# GaN_LLC.net
KiCad netlist of a schematic drawn in Altium Designer
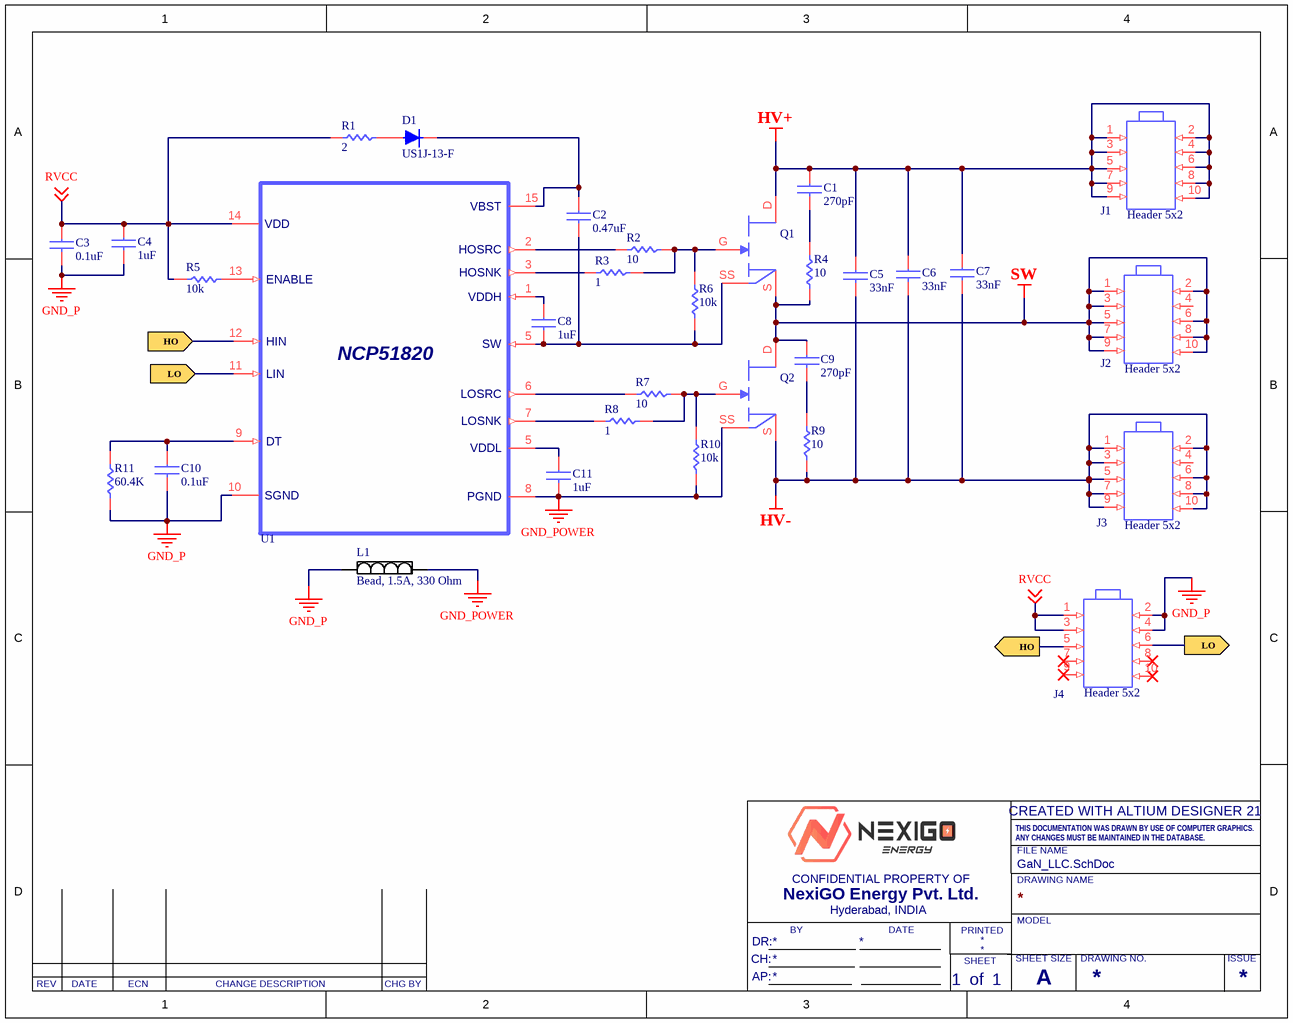
[diagram p0: GaN_LLC.SchDoc]

(export (version "E")
  (design (tool "Eeschema 10.0.6"))
  (components
    (comp (ref "C1")
      (value "270pF")
      (footprint "1206")
      (description "CAP CER 270PF 1KV C0G/NP0 1206")
      (fields (field (name "TOLERANCE") "±5%") (field (name "MANUFACTURER") "Samsung Electro-Mechanics"))
      (libsource (lib "NexiGOEnergyPartsDatabaseLibrary") (part "CAP_CERAMIC"))
    )
    (comp (ref "C2")
      (value "0.47uF")
      (footprint "Cap, 0603")
      (description "CAP CER 0.47UF 25V 10% X7R 0603")
      (fields (field (name "TOLERANCE") "10%") (field (name "MANUFACTURER") "AVX Corporation"))
      (libsource (lib "NexiGOEnergyPartsDatabaseLibrary") (part "CAP_CERAMIC"))
    )
    (comp (ref "C3")
      (value "0.1uF")
      (footprint "Cap, 0603")
      (description "CAP CER 0.1UF 50V 10% X7R 0603")
      (fields (field (name "TOLERANCE") "10%") (field (name "MANUFACTURER") "TAIYO YUDEN"))
      (libsource (lib "NexiGOEnergyPartsDatabaseLibrary") (part "CAP_CERAMIC"))
    )
    (comp (ref "C4")
      (value "1uF")
      (footprint "Cap, 0603")
      (description "CAP CER 1UF 25V 10% X7R 0603")
      (fields (field (name "TOLERANCE") "10%") (field (name "MANUFACTURER") "Samsung Electro-Mechanics"))
      (libsource (lib "NexiGOEnergyPartsDatabaseLibrary") (part "CAP_CERAMIC"))
    )
    (comp (ref "C5")
      (value "33nF")
      (footprint "1210")
      (description "CAP CER 0.033UF 1.5KV X7R 1210")
      (fields (field (name "TOLERANCE") "10%") (field (name "MANUFACTURER") "KEMET"))
      (libsource (lib "NexiGOEnergyPartsDatabaseLibrary") (part "CAP_CERAMIC"))
    )
    (comp (ref "C6")
      (value "33nF")
      (footprint "1210")
      (description "CAP CER 0.033UF 1.5KV X7R 1210")
      (fields (field (name "TOLERANCE") "10%") (field (name "MANUFACTURER") "KEMET"))
      (libsource (lib "NexiGOEnergyPartsDatabaseLibrary") (part "CAP_CERAMIC"))
    )
    (comp (ref "C7")
      (value "33nF")
      (footprint "1210")
      (description "CAP CER 0.033UF 1.5KV X7R 1210")
      (fields (field (name "TOLERANCE") "10%") (field (name "MANUFACTURER") "KEMET"))
      (libsource (lib "NexiGOEnergyPartsDatabaseLibrary") (part "CAP_CERAMIC"))
    )
    (comp (ref "C8")
      (value "1uF")
      (footprint "Cap, 0603")
      (description "CAP CER 1UF 25V 10% X7R 0603")
      (fields (field (name "TOLERANCE") "10%") (field (name "MANUFACTURER") "Samsung Electro-Mechanics"))
      (libsource (lib "NexiGOEnergyPartsDatabaseLibrary") (part "CAP_CERAMIC"))
    )
    (comp (ref "C9")
      (value "270pF")
      (footprint "1206")
      (description "CAP CER 270PF 1KV C0G/NP0 1206")
      (fields (field (name "TOLERANCE") "±5%") (field (name "MANUFACTURER") "Samsung Electro-Mechanics"))
      (libsource (lib "NexiGOEnergyPartsDatabaseLibrary") (part "CAP_CERAMIC"))
    )
    (comp (ref "C10")
      (value "0.1uF")
      (footprint "Cap, 0603")
      (description "CAP CER 0.1UF 50V 10% X7R 0603")
      (fields (field (name "TOLERANCE") "10%") (field (name "MANUFACTURER") "TAIYO YUDEN"))
      (libsource (lib "NexiGOEnergyPartsDatabaseLibrary") (part "CAP_CERAMIC"))
    )
    (comp (ref "C11")
      (value "1uF")
      (footprint "Cap, 0603")
      (description "CAP CER 1UF 25V 10% X7R 0603")
      (fields (field (name "TOLERANCE") "10%") (field (name "MANUFACTURER") "Samsung Electro-Mechanics"))
      (libsource (lib "NexiGOEnergyPartsDatabaseLibrary") (part "CAP_CERAMIC"))
    )
    (comp (ref "D1")
      (value "US1J-13-F")
      (footprint "SMA")
      (description "DIODE GEN PURP 600V 1A SMA")
      (fields (field (name "MANUFACTURER") "Diodes Incorporated") (field (name "Comment") "Diode"))
      (libsource (lib "NexiGOEnergyPartsDatabaseLibrary") (part "Diode"))
    )
    (comp (ref "J1")
      (value "Header 5x2")
      (footprint "HDR2X5_SMD")
      (description "HEADER 5X2 2MM Pitch SMT")
      (fields
        (field (name "MANUFACTURER") "Sullins Connector Solutions")
        (field (name "Comment") "Header 5x2, 100Mils")
      )
      (libsource (lib "NexiGOEnergyPartsDatabaseLibrary") (part "Header 5x2, 100Mils"))
    )
    (comp (ref "J2")
      (value "Header 5x2")
      (footprint "HDR2X5_SMD")
      (description "HEADER 5X2 2MM Pitch SMT")
      (fields
        (field (name "MANUFACTURER") "Sullins Connector Solutions")
        (field (name "Comment") "Header 5x2, 100Mils")
      )
      (libsource (lib "NexiGOEnergyPartsDatabaseLibrary") (part "Header 5x2, 100Mils"))
    )
    (comp (ref "J3")
      (value "Header 5x2")
      (footprint "HDR2X5_SMD")
      (description "HEADER 5X2 2MM Pitch SMT")
      (fields
        (field (name "MANUFACTURER") "Sullins Connector Solutions")
        (field (name "Comment") "Header 5x2, 100Mils")
      )
      (libsource (lib "NexiGOEnergyPartsDatabaseLibrary") (part "Header 5x2, 100Mils"))
    )
    (comp (ref "J4")
      (value "Header 5x2")
      (footprint "HDR2X5_SMD")
      (description "HEADER 5X2 2MM Pitch SMT")
      (fields
        (field (name "MANUFACTURER") "Sullins Connector Solutions")
        (field (name "Comment") "Header 5x2, 100Mils")
      )
      (libsource (lib "NexiGOEnergyPartsDatabaseLibrary") (part "Header 5x2, 100Mils"))
    )
    (comp (ref "L1")
      (value "Bead, 1.5A, 330 Ohm")
      (footprint "0603")
      (description "FERRITE BEAD 330 OHM 1.5A 0603")
      (fields (field (name "MANUFACTURER") "Murata") (field (name "Comment") "Bead, 6A, 33 Ohm"))
      (libsource (lib "NexiGOEnergyPartsDatabaseLibrary") (part "Bead, 6A, 33 Ohm"))
    )
    (comp (ref "Q1")
      (value "GS66508B")
      (footprint "GS66508B")
      (description "GS66508B GaN FET 650V 30A 50mOhm SMT")
      (fields (field (name "MANUFACTURER") "GaN Systems"))
      (libsource (lib "NexiGOEnergyPartsDatabaseLibrary") (part "GS66508B"))
    )
    (comp (ref "Q2")
      (value "GS66508B")
      (footprint "GS66508B")
      (description "GS66508B GaN FET 650V 30A 50mOhm SMT")
      (fields (field (name "MANUFACTURER") "GaN Systems"))
      (libsource (lib "NexiGOEnergyPartsDatabaseLibrary") (part "GS66508B"))
    )
    (comp (ref "R1")
      (value "2")
      (footprint "Res, 0603")
      (description "RES 2 OHM 1/10W 1% 0603 SMD")
      (fields (field (name "MANUFACTURER") "Vishay / Dale") (field (name "TOLERANCE") "±1%"))
      (libsource (lib "NexiGOEnergyPartsDatabaseLibrary") (part "Res"))
    )
    (comp (ref "R2")
      (value "10")
      (footprint "Res, 0603")
      (description "Res, 10, 1%, 0603,1/10W, Panasonic, 100ppm")
      (fields (field (name "MANUFACTURER") "Panasonic") (field (name "TOLERANCE") "±1%"))
      (libsource (lib "NexiGOEnergyPartsDatabaseLibrary") (part "Res"))
    )
    (comp (ref "R3")
      (value "1")
      (footprint "Res, 0603")
      (description "RES 1 OHM 1/10W 0603")
      (fields (field (name "MANUFACTURER") "Vishay/Dale") (field (name "TOLERANCE") "±1%"))
      (libsource (lib "NexiGOEnergyPartsDatabaseLibrary") (part "Res"))
    )
    (comp (ref "R4")
      (value "10")
      (footprint "Res_2512")
      (description "RES 10 OHM 5% 2W 2512")
      (fields (field (name "MANUFACTURER") "YAGEO") (field (name "TOLERANCE") "5%"))
      (libsource (lib "NexiGOEnergyPartsDatabaseLibrary") (part "Res"))
    )
    (comp (ref "R5")
      (value "10k")
      (footprint "Res, 0603")
      (description "Res, 10K, 1%, 0603,1/10W, Panasonic, 100ppm")
      (fields (field (name "MANUFACTURER") "Panasonic") (field (name "TOLERANCE") "±1%"))
      (libsource (lib "NexiGOEnergyPartsDatabaseLibrary") (part "Res"))
    )
    (comp (ref "R6")
      (value "10k")
      (footprint "Res, 0603")
      (description "Res, 10K, 1%, 0603,1/10W, Panasonic, 100ppm")
      (fields (field (name "MANUFACTURER") "Panasonic") (field (name "TOLERANCE") "±1%"))
      (libsource (lib "NexiGOEnergyPartsDatabaseLibrary") (part "Res"))
    )
    (comp (ref "R7")
      (value "10")
      (footprint "Res, 0603")
      (description "Res, 10, 1%, 0603,1/10W, Panasonic, 100ppm")
      (fields (field (name "MANUFACTURER") "Panasonic") (field (name "TOLERANCE") "±1%"))
      (libsource (lib "NexiGOEnergyPartsDatabaseLibrary") (part "Res"))
    )
    (comp (ref "R8")
      (value "1")
      (footprint "Res, 0603")
      (description "RES 1 OHM 1/10W 0603")
      (fields (field (name "MANUFACTURER") "Vishay/Dale") (field (name "TOLERANCE") "±1%"))
      (libsource (lib "NexiGOEnergyPartsDatabaseLibrary") (part "Res"))
    )
    (comp (ref "R9")
      (value "10")
      (footprint "Res_2512")
      (description "RES 10 OHM 5% 2W 2512")
      (fields (field (name "MANUFACTURER") "YAGEO") (field (name "TOLERANCE") "5%"))
      (libsource (lib "NexiGOEnergyPartsDatabaseLibrary") (part "Res"))
    )
    (comp (ref "R10")
      (value "10k")
      (footprint "Res, 0603")
      (description "Res, 10K, 1%, 0603,1/10W, Panasonic, 100ppm")
      (fields (field (name "MANUFACTURER") "Panasonic") (field (name "TOLERANCE") "±1%"))
      (libsource (lib "NexiGOEnergyPartsDatabaseLibrary") (part "Res"))
    )
    (comp (ref "R11")
      (value "60.4K")
      (footprint "Res, 0603")
      (description "RES 60.4K OHM 1/10W 1% 0603 SMD")
      (fields (field (name "MANUFACTURER") "Panasonic") (field (name "TOLERANCE") "±1%"))
      (libsource (lib "NexiGOEnergyPartsDatabaseLibrary") (part "Res"))
    )
    (comp (ref "U1")
      (value "NCP51820")
      (footprint "QFN_0AMNTWG_ONS")
      (description "NCP51820 FULL BRIDGE GATE DRIVE 15QFN SMD")
      (fields (field (name "MANUFACTURER") "Onsemi"))
      (libsource (lib "NexiGOEnergyPartsDatabaseLibrary") (part "NCP51820"))
    )
  )
  (nets
    (net (code "1") (name "/HO") (class "Default")
      (node (ref "J4") (pin "5") (pintype "input"))
      (node (ref "U1") (pin "12") (pinfunction "HIN_12") (pintype "input"))
    )
    (net (code "2") (name "/LO") (class "Default")
      (node (ref "J4") (pin "6") (pintype "input"))
      (node (ref "U1") (pin "11") (pinfunction "LIN_11") (pintype "input"))
    )
    (net (code "3") (name "GND_P") (class "Default")
      (node (ref "C10") (pin "2") (pinfunction "2_2") (pintype "passive"))
      (node (ref "C3") (pin "2") (pinfunction "2_2") (pintype "passive"))
      (node (ref "C4") (pin "2") (pinfunction "2_2") (pintype "passive"))
      (node (ref "J4") (pin "2") (pintype "input"))
      (node (ref "J4") (pin "4") (pintype "input"))
      (node (ref "L1") (pin "1") (pinfunction "1_1") (pintype "passive"))
      (node (ref "R11") (pin "1") (pinfunction "1_1") (pintype "passive"))
      (node (ref "U1") (pin "10") (pinfunction "SGND_10") (pintype "power_in"))
    )
    (net (code "4") (name "GND_POWER") (class "Default")
      (node (ref "C11") (pin "2") (pinfunction "2_2") (pintype "passive"))
      (node (ref "L1") (pin "2") (pinfunction "2_2") (pintype "passive"))
      (node (ref "Q2") (pin "SS") (pinfunction "SS_SS") (pintype "passive"))
      (node (ref "R10") (pin "1") (pinfunction "1_1") (pintype "passive"))
      (node (ref "U1") (pin "8") (pinfunction "PGND_8") (pintype "power_in"))
    )
    (net (code "5") (name "HV+") (class "Default")
      (node (ref "C1") (pin "1") (pinfunction "1_1") (pintype "passive"))
      (node (ref "C5") (pin "1") (pinfunction "1_1") (pintype "passive"))
      (node (ref "C6") (pin "1") (pinfunction "1_1") (pintype "passive"))
      (node (ref "C7") (pin "1") (pinfunction "1_1") (pintype "passive"))
      (node (ref "J1") (pin "1") (pintype "input"))
      (node (ref "J1") (pin "10") (pintype "input"))
      (node (ref "J1") (pin "2") (pintype "input"))
      (node (ref "J1") (pin "3") (pintype "input"))
      (node (ref "J1") (pin "4") (pintype "input"))
      (node (ref "J1") (pin "5") (pintype "input"))
      (node (ref "J1") (pin "6") (pintype "input"))
      (node (ref "J1") (pin "7") (pintype "input"))
      (node (ref "J1") (pin "8") (pintype "input"))
      (node (ref "J1") (pin "9") (pintype "input"))
      (node (ref "Q1") (pin "D") (pinfunction "D_D") (pintype "passive"))
    )
    (net (code "6") (name "HV-") (class "Default")
      (node (ref "C5") (pin "2") (pinfunction "2_2") (pintype "passive"))
      (node (ref "C6") (pin "2") (pinfunction "2_2") (pintype "passive"))
      (node (ref "C7") (pin "2") (pinfunction "2_2") (pintype "passive"))
      (node (ref "J3") (pin "1") (pintype "input"))
      (node (ref "J3") (pin "10") (pintype "input"))
      (node (ref "J3") (pin "2") (pintype "input"))
      (node (ref "J3") (pin "3") (pintype "input"))
      (node (ref "J3") (pin "5") (pintype "input"))
      (node (ref "J3") (pin "6") (pintype "input"))
      (node (ref "J3") (pin "7") (pintype "input"))
      (node (ref "J3") (pin "8") (pintype "input"))
      (node (ref "J3") (pin "9") (pintype "input"))
      (node (ref "Q2") (pin "S") (pinfunction "S_S") (pintype "passive"))
      (node (ref "R9") (pin "1") (pinfunction "1_1") (pintype "passive"))
    )
    (net (code "7") (name "Net-(C1-Pad2)") (class "Default")
      (node (ref "C1") (pin "2") (pinfunction "2_2") (pintype "passive"))
      (node (ref "R4") (pin "2") (pinfunction "2_2") (pintype "passive"))
    )
    (net (code "8") (name "Net-(C9-Pad2)") (class "Default")
      (node (ref "C9") (pin "2") (pinfunction "2_2") (pintype "passive"))
      (node (ref "R9") (pin "2") (pinfunction "2_2") (pintype "passive"))
    )
    (net (code "9") (name "Net-(D1-Pad2)") (class "Default")
      (node (ref "D1") (pin "2") (pinfunction "2_2") (pintype "passive"))
      (node (ref "R1") (pin "2") (pinfunction "2_2") (pintype "passive"))
    )
    (net (code "10") (name "Net-(Q1-PadG)") (class "Default")
      (node (ref "Q1") (pin "G") (pinfunction "G_G") (pintype "passive"))
      (node (ref "R2") (pin "2") (pinfunction "2_2") (pintype "passive"))
      (node (ref "R3") (pin "2") (pinfunction "2_2") (pintype "passive"))
      (node (ref "R6") (pin "2") (pinfunction "2_2") (pintype "passive"))
    )
    (net (code "11") (name "Net-(Q2-PadG)") (class "Default")
      (node (ref "Q2") (pin "G") (pinfunction "G_G") (pintype "passive"))
      (node (ref "R10") (pin "2") (pinfunction "2_2") (pintype "passive"))
      (node (ref "R7") (pin "2") (pinfunction "2_2") (pintype "passive"))
      (node (ref "R8") (pin "2") (pinfunction "2_2") (pintype "passive"))
    )
    (net (code "12") (name "Net-(U1-DT)") (class "Default")
      (node (ref "C10") (pin "1") (pinfunction "1_1") (pintype "passive"))
      (node (ref "R11") (pin "2") (pinfunction "2_2") (pintype "passive"))
      (node (ref "U1") (pin "9") (pinfunction "DT_9") (pintype "input"))
    )
    (net (code "13") (name "Net-(U1-ENABLE)") (class "Default")
      (node (ref "R5") (pin "1") (pinfunction "1_1") (pintype "passive"))
      (node (ref "U1") (pin "13") (pinfunction "ENABLE_13") (pintype "input"))
    )
    (net (code "14") (name "Net-(U1-HOSNK)") (class "Default")
      (node (ref "R3") (pin "1") (pinfunction "1_1") (pintype "passive"))
      (node (ref "U1") (pin "3") (pinfunction "HOSNK_3") (pintype "output"))
    )
    (net (code "15") (name "Net-(U1-HOSRC)") (class "Default")
      (node (ref "R2") (pin "1") (pinfunction "1_1") (pintype "passive"))
      (node (ref "U1") (pin "2") (pinfunction "HOSRC_2") (pintype "output"))
    )
    (net (code "16") (name "Net-(U1-LOSNK)") (class "Default")
      (node (ref "R8") (pin "1") (pinfunction "1_1") (pintype "passive"))
      (node (ref "U1") (pin "7") (pinfunction "LOSNK_7") (pintype "output"))
    )
    (net (code "17") (name "Net-(U1-LOSRC)") (class "Default")
      (node (ref "R7") (pin "1") (pinfunction "1_1") (pintype "passive"))
      (node (ref "U1") (pin "6") (pinfunction "LOSRC_6") (pintype "output"))
    )
    (net (code "18") (name "Net-(U1-SW)") (class "Default")
      (node (ref "C2") (pin "2") (pinfunction "2_2") (pintype "passive"))
      (node (ref "C8") (pin "2") (pinfunction "2_2") (pintype "passive"))
      (node (ref "Q1") (pin "SS") (pinfunction "SS_SS") (pintype "passive"))
      (node (ref "R6") (pin "1") (pinfunction "1_1") (pintype "passive"))
      (node (ref "U1") (pin "5") (pinfunction "SW_5") (pintype "input"))
    )
    (net (code "19") (name "Net-(U1-VBST)") (class "Default")
      (node (ref "C2") (pin "1") (pinfunction "1_1") (pintype "passive"))
      (node (ref "D1") (pin "1") (pinfunction "1_1") (pintype "passive"))
      (node (ref "U1") (pin "15") (pinfunction "VBST_15") (pintype "power_in"))
    )
    (net (code "20") (name "Net-(U1-VDDH)") (class "Default")
      (node (ref "C8") (pin "1") (pinfunction "1_1") (pintype "passive"))
      (node (ref "U1") (pin "1") (pinfunction "VDDH_1") (pintype "input"))
    )
    (net (code "21") (name "Net-(U1-VDDL)") (class "Default")
      (node (ref "C11") (pin "1") (pinfunction "1_1") (pintype "passive"))
      (node (ref "U1") (pin "5") (pinfunction "VDDL_5") (pintype "power_in"))
    )
    (net (code "22") (name "RVCC") (class "Default")
      (node (ref "C3") (pin "1") (pinfunction "1_1") (pintype "passive"))
      (node (ref "C4") (pin "1") (pinfunction "1_1") (pintype "passive"))
      (node (ref "J4") (pin "1") (pintype "input"))
      (node (ref "J4") (pin "3") (pintype "input"))
      (node (ref "R1") (pin "1") (pinfunction "1_1") (pintype "passive"))
      (node (ref "R5") (pin "2") (pinfunction "2_2") (pintype "passive"))
      (node (ref "U1") (pin "14") (pinfunction "VDD_14") (pintype "power_in"))
    )
    (net (code "23") (name "SW") (class "Default")
      (node (ref "C9") (pin "1") (pinfunction "1_1") (pintype "passive"))
      (node (ref "J2") (pin "1") (pintype "input"))
      (node (ref "J2") (pin "10") (pintype "input"))
      (node (ref "J2") (pin "2") (pintype "input"))
      (node (ref "J2") (pin "3") (pintype "input"))
      (node (ref "J2") (pin "5") (pintype "input"))
      (node (ref "J2") (pin "6") (pintype "input"))
      (node (ref "J2") (pin "7") (pintype "input"))
      (node (ref "J2") (pin "8") (pintype "input"))
      (node (ref "J2") (pin "9") (pintype "input"))
      (node (ref "Q1") (pin "S") (pinfunction "S_S") (pintype "passive"))
      (node (ref "Q2") (pin "D") (pinfunction "D_D") (pintype "passive"))
      (node (ref "R4") (pin "1") (pinfunction "1_1") (pintype "passive"))
    )
    (net (code "24") (name "unconnected-(J2-Pad4)") (class "Default")
      (node (ref "J2") (pin "4") (pintype "input"))
    )
    (net (code "25") (name "unconnected-(J3-Pad4)") (class "Default")
      (node (ref "J3") (pin "4") (pintype "input"))
    )
    (net (code "26") (name "unconnected-(J4-Pad7)") (class "Default")
      (node (ref "J4") (pin "7") (pintype "input+no_connect"))
    )
    (net (code "27") (name "unconnected-(J4-Pad8)") (class "Default")
      (node (ref "J4") (pin "8") (pintype "input+no_connect"))
    )
    (net (code "28") (name "unconnected-(J4-Pad9)") (class "Default")
      (node (ref "J4") (pin "9") (pintype "input+no_connect"))
    )
    (net (code "29") (name "unconnected-(J4-Pad10)") (class "Default")
      (node (ref "J4") (pin "10") (pintype "input+no_connect"))
    )
  )
)
